# diyhue-IO.net
KiCad netlist of a schematic drawn in EAGLE
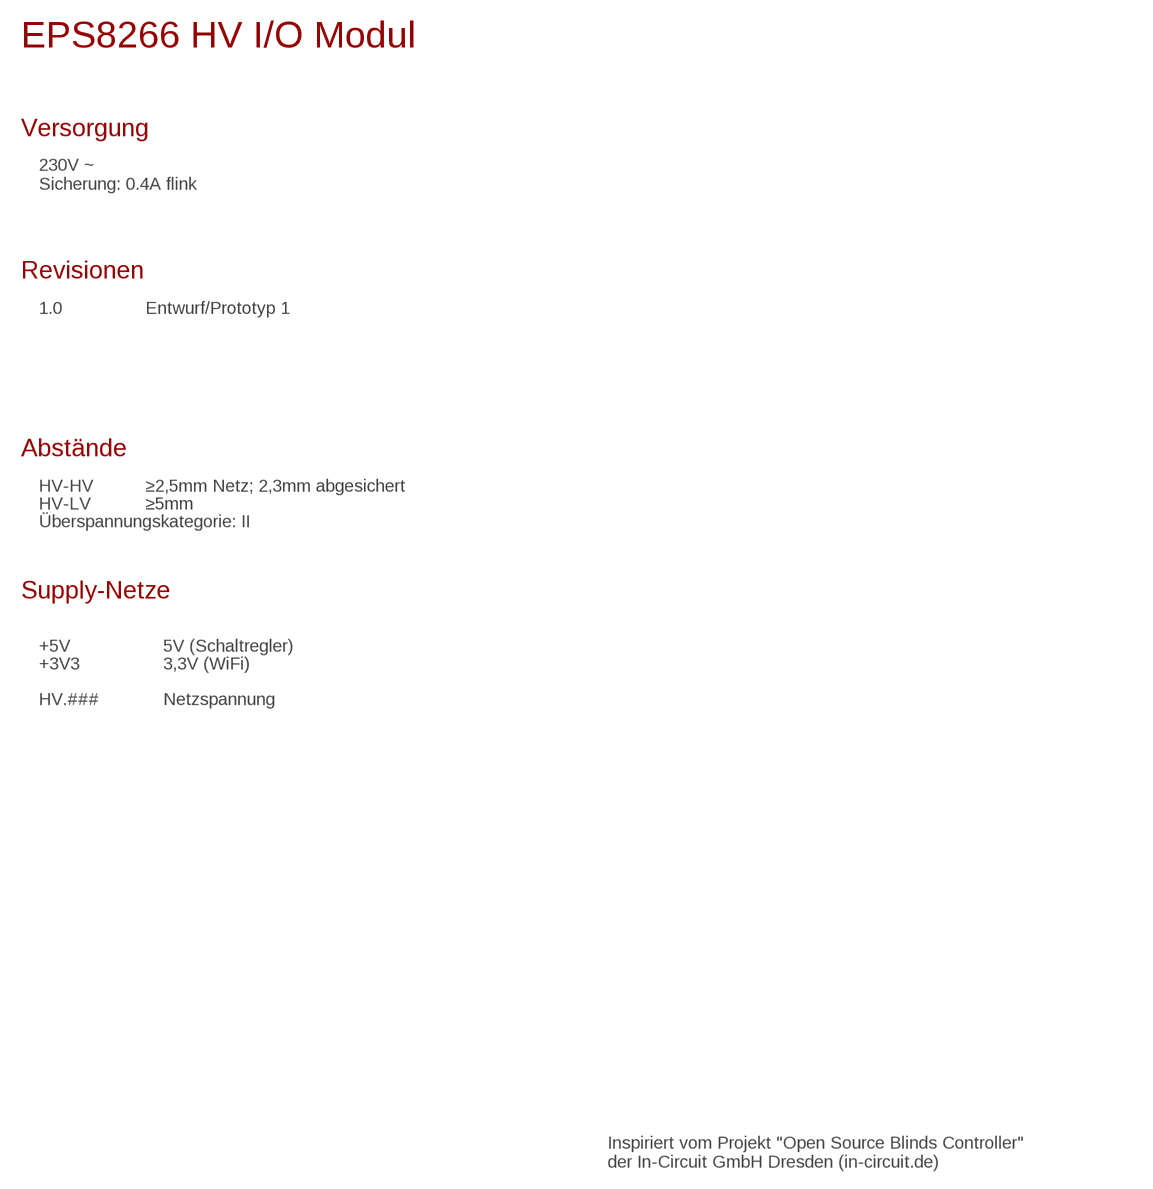
[diagram p0: schematic, sheet 1]
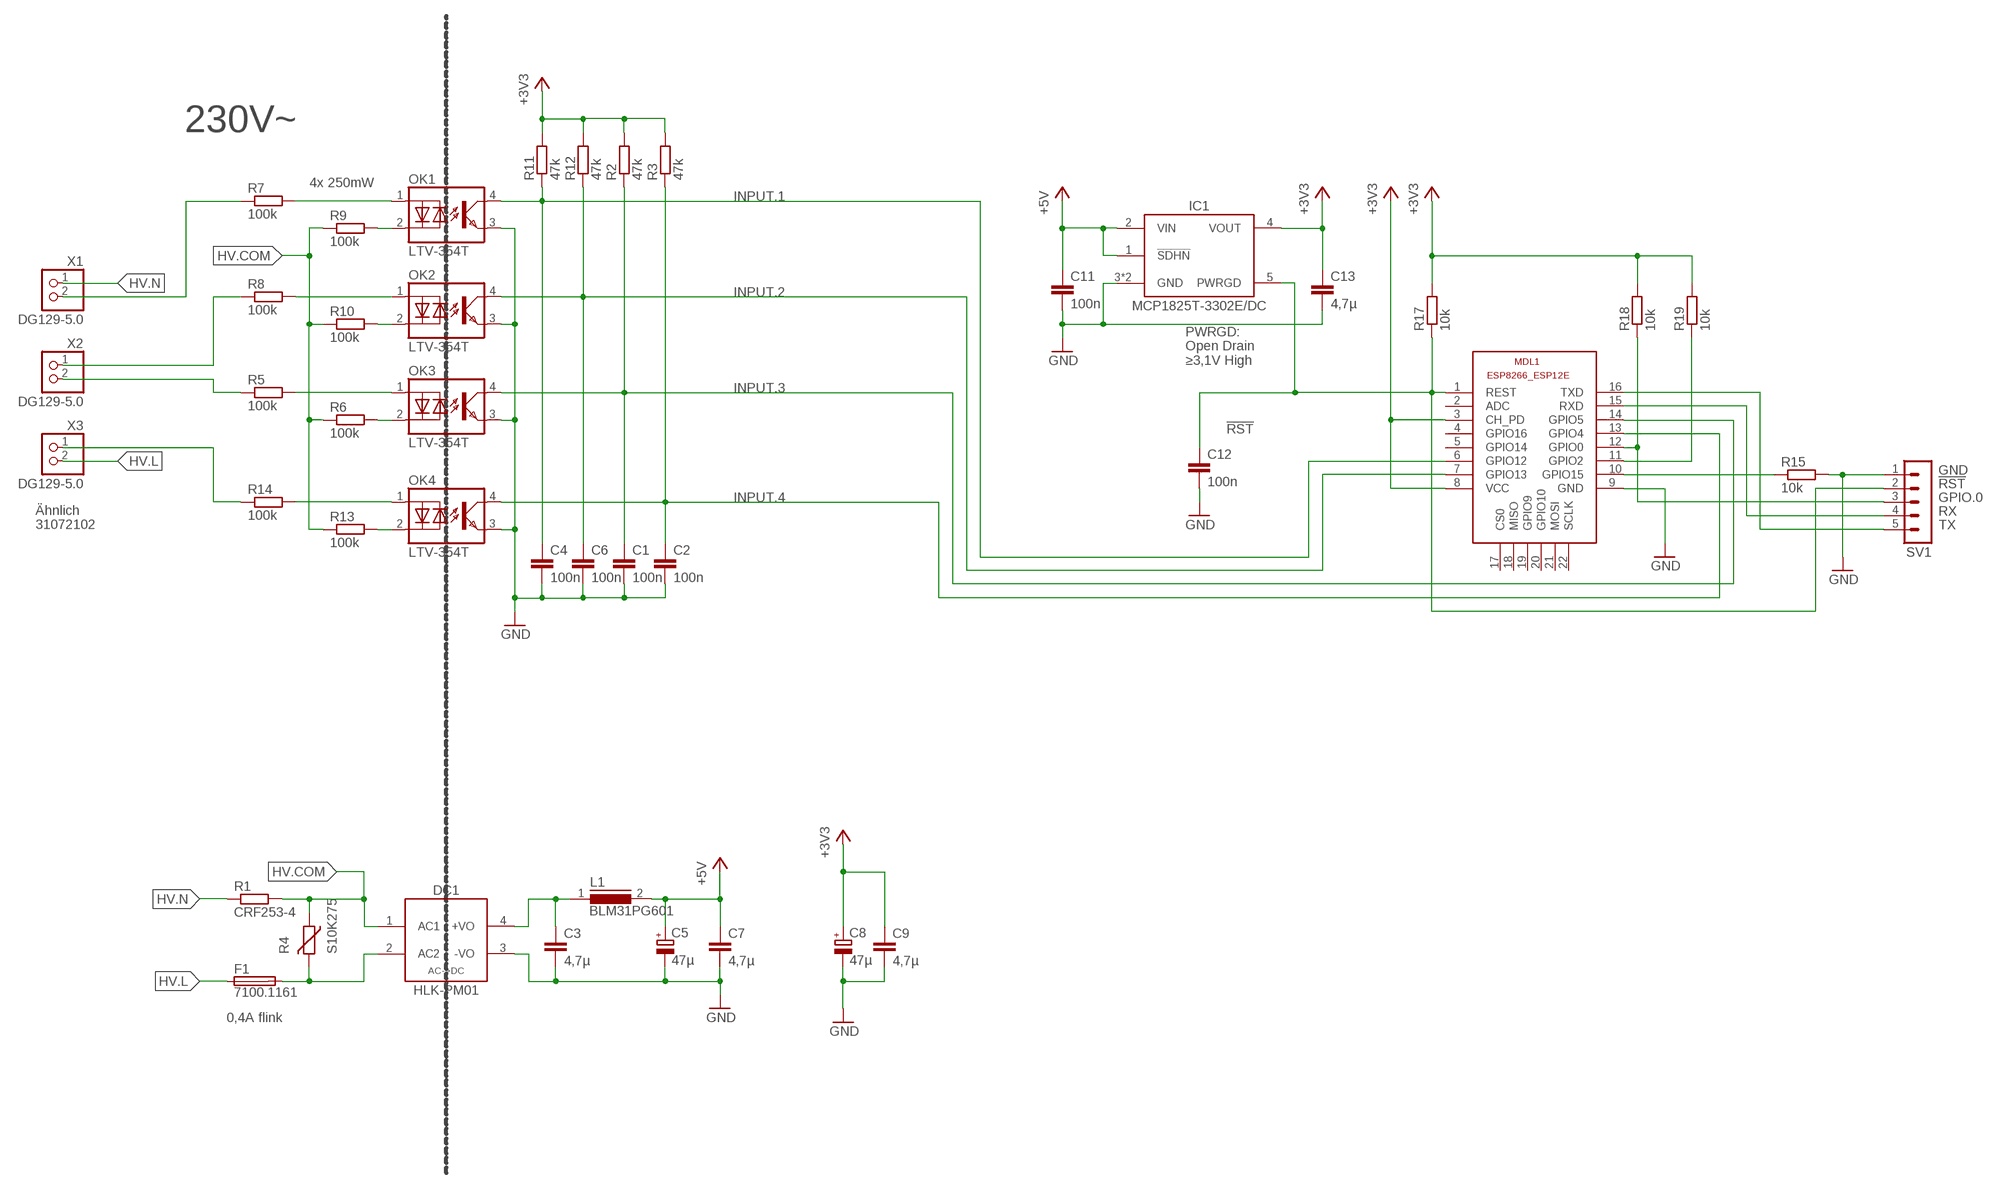
[diagram p1: schematic, sheet 2]

(export (version "E")
  (design (tool "Eeschema 10.0.6"))
  (components
    (comp (ref "C1")
      (value "100n")
      (footprint "eagle-import:C0805K")
      (libsource (lib "eagle-import") (part "C-EUC0805K"))
    )
    (comp (ref "C2")
      (value "100n")
      (footprint "eagle-import:C0805K")
      (libsource (lib "eagle-import") (part "C-EUC0805K"))
    )
    (comp (ref "C3")
      (value "4,7µ")
      (footprint "eagle-import:C0805K")
      (libsource (lib "eagle-import") (part "C-EUC0805K"))
    )
    (comp (ref "C4")
      (value "100n")
      (footprint "eagle-import:C0805K")
      (libsource (lib "eagle-import") (part "C-EUC0805K"))
    )
    (comp (ref "C5")
      (value "47µ")
      (footprint "eagle-import:E2-5")
      (libsource (lib "eagle-import") (part "CPOL-EUE2-5"))
    )
    (comp (ref "C6")
      (value "100n")
      (footprint "eagle-import:C0805K")
      (libsource (lib "eagle-import") (part "C-EUC0805K"))
    )
    (comp (ref "C7")
      (value "4,7µ")
      (footprint "eagle-import:C0805K")
      (libsource (lib "eagle-import") (part "C-EUC0805K"))
    )
    (comp (ref "C8")
      (value "47µ")
      (footprint "eagle-import:E2-5")
      (libsource (lib "eagle-import") (part "CPOL-EUE2-5"))
    )
    (comp (ref "C9")
      (value "4,7µ")
      (footprint "eagle-import:C0805K")
      (libsource (lib "eagle-import") (part "C-EUC0805K"))
    )
    (comp (ref "C11")
      (value "100n")
      (footprint "eagle-import:C0805K")
      (libsource (lib "eagle-import") (part "C-EUC0805K"))
    )
    (comp (ref "C12")
      (value "100n")
      (footprint "eagle-import:C0805K")
      (libsource (lib "eagle-import") (part "C-EUC0805K"))
    )
    (comp (ref "C13")
      (value "4,7µ")
      (footprint "eagle-import:C0805K")
      (libsource (lib "eagle-import") (part "C-EUC0805K"))
    )
    (comp (ref "DC1")
      (value "HLK-PM01")
      (footprint "eagle-import:HLK_PM01")
      (libsource (lib "eagle-import") (part "ACDC-S-HLK_PM01"))
    )
    (comp (ref "F1")
      (value "7100.1161")
      (footprint "eagle-import:SCHURTER_FRT250")
      (libsource (lib "eagle-import") (part "FUSE-FRT250"))
    )
    (comp (ref "IC1")
      (value "MCP1825T-3302E/DC")
      (footprint "eagle-import:SOT-223_5")
      (libsource (lib "eagle-import") (part "MCP1825/DC"))
    )
    (comp (ref "L1")
      (value "BLM31PG601")
      (footprint "eagle-import:BLM31P")
      (libsource (lib "eagle-import") (part "INDUCTOR-BLM31"))
    )
    (comp (ref "MDL1")
      (value "ESP8266-12EESP8266-ESP12E")
      (footprint "eagle-import:ESP8266-ESP12E")
      (libsource (lib "eagle-import") (part "ESP8266-12EESP8266-ESP12E"))
    )
    (comp (ref "OK1")
      (value "LTV-354T")
      (footprint "eagle-import:LITEON_LTV-354")
      (libsource (lib "eagle-import") (part "OC-AC_LTV-354"))
    )
    (comp (ref "OK2")
      (value "LTV-354T")
      (footprint "eagle-import:LITEON_LTV-354")
      (libsource (lib "eagle-import") (part "OC-AC_LTV-354"))
    )
    (comp (ref "OK3")
      (value "LTV-354T")
      (footprint "eagle-import:LITEON_LTV-354")
      (libsource (lib "eagle-import") (part "OC-AC_LTV-354"))
    )
    (comp (ref "OK4")
      (value "LTV-354T")
      (footprint "eagle-import:LITEON_LTV-354")
      (libsource (lib "eagle-import") (part "OC-AC_LTV-354"))
    )
    (comp (ref "R1")
      (value "CRF253-4")
      (footprint "eagle-import:0414V")
      (libsource (lib "eagle-import") (part "R-EU_0414/5V"))
    )
    (comp (ref "R2")
      (value "47k")
      (footprint "eagle-import:R0805W")
      (libsource (lib "eagle-import") (part "rcl_334_R-EU_R0805W"))
    )
    (comp (ref "R3")
      (value "47k")
      (footprint "eagle-import:R0805W")
      (libsource (lib "eagle-import") (part "rcl_334_R-EU_R0805W"))
    )
    (comp (ref "R4")
      (value "S10K275")
      (footprint "eagle-import:EPCOS_S10K275")
      (libsource (lib "eagle-import") (part "VDR-S10K275"))
    )
    (comp (ref "R5")
      (value "100k")
      (footprint "eagle-import:R1210")
      (libsource (lib "eagle-import") (part "rcl_334_R-EU_R1210"))
    )
    (comp (ref "R6")
      (value "100k")
      (footprint "eagle-import:R1210")
      (libsource (lib "eagle-import") (part "rcl_334_R-EU_R1210"))
    )
    (comp (ref "R7")
      (value "100k")
      (footprint "eagle-import:R1210")
      (libsource (lib "eagle-import") (part "rcl_334_R-EU_R1210"))
    )
    (comp (ref "R8")
      (value "100k")
      (footprint "eagle-import:R1210")
      (libsource (lib "eagle-import") (part "rcl_334_R-EU_R1210"))
    )
    (comp (ref "R9")
      (value "100k")
      (footprint "eagle-import:R1210")
      (libsource (lib "eagle-import") (part "rcl_334_R-EU_R1210"))
    )
    (comp (ref "R10")
      (value "100k")
      (footprint "eagle-import:R1210")
      (libsource (lib "eagle-import") (part "rcl_334_R-EU_R1210"))
    )
    (comp (ref "R11")
      (value "47k")
      (footprint "eagle-import:R0805W")
      (libsource (lib "eagle-import") (part "rcl_334_R-EU_R0805W"))
    )
    (comp (ref "R12")
      (value "47k")
      (footprint "eagle-import:R0805W")
      (libsource (lib "eagle-import") (part "rcl_334_R-EU_R0805W"))
    )
    (comp (ref "R13")
      (value "100k")
      (footprint "eagle-import:R1210")
      (libsource (lib "eagle-import") (part "rcl_334_R-EU_R1210"))
    )
    (comp (ref "R14")
      (value "100k")
      (footprint "eagle-import:R1210")
      (libsource (lib "eagle-import") (part "rcl_334_R-EU_R1210"))
    )
    (comp (ref "R15")
      (value "10k")
      (footprint "eagle-import:R0805W")
      (libsource (lib "eagle-import") (part "rcl_334_R-EU_R0805W"))
    )
    (comp (ref "R17")
      (value "10k")
      (footprint "eagle-import:R0805W")
      (libsource (lib "eagle-import") (part "rcl_334_R-EU_R0805W"))
    )
    (comp (ref "R18")
      (value "10k")
      (footprint "eagle-import:R0805W")
      (libsource (lib "eagle-import") (part "rcl_334_R-EU_R0805W"))
    )
    (comp (ref "R19")
      (value "10k")
      (footprint "eagle-import:R0805W")
      (libsource (lib "eagle-import") (part "rcl_334_R-EU_R0805W"))
    )
    (comp (ref "SV1")
      (value "MA05-1")
      (footprint "eagle-import:MA05-1")
      (libsource (lib "eagle-import") (part "MA05-1"))
    )
    (comp (ref "X1")
      (value "DG129-5.0")
      (footprint "eagle-import:31012102")
      (libsource (lib "eagle-import") (part "1PIN-2-31012102"))
    )
    (comp (ref "X2")
      (value "DG129-5.0")
      (footprint "eagle-import:31012102")
      (libsource (lib "eagle-import") (part "1PIN-2-31012102"))
    )
    (comp (ref "X3")
      (value "DG129-5.0")
      (footprint "eagle-import:31012102")
      (libsource (lib "eagle-import") (part "1PIN-2-31012102"))
    )
  )
  (nets
    (net (code "1") (name "+3V3") (class "Default")
      (node (ref "C13") (pin "1") (pinfunction "1_1") (pintype "passive"))
      (node (ref "C8") (pin "+") (pinfunction "+_+") (pintype "passive"))
      (node (ref "C9") (pin "1") (pinfunction "1_1") (pintype "passive"))
      (node (ref "IC1") (pin "4") (pinfunction "VOUT_4") (pintype "passive"))
      (node (ref "MDL1") (pin "3") (pinfunction "CH_PD_3") (pintype "bidirectional"))
      (node (ref "MDL1") (pin "8") (pinfunction "VCC_8") (pintype "bidirectional"))
      (node (ref "R11") (pin "2") (pinfunction "2_2") (pintype "passive"))
      (node (ref "R12") (pin "2") (pinfunction "2_2") (pintype "passive"))
      (node (ref "R17") (pin "2") (pinfunction "2_2") (pintype "passive"))
      (node (ref "R18") (pin "2") (pinfunction "2_2") (pintype "passive"))
      (node (ref "R19") (pin "2") (pinfunction "2_2") (pintype "passive"))
      (node (ref "R2") (pin "2") (pinfunction "2_2") (pintype "passive"))
      (node (ref "R3") (pin "2") (pinfunction "2_2") (pintype "passive"))
    )
    (net (code "2") (name "+5V") (class "Default")
      (node (ref "C11") (pin "1") (pinfunction "1_1") (pintype "passive"))
      (node (ref "C5") (pin "+") (pinfunction "+_+") (pintype "passive"))
      (node (ref "C7") (pin "1") (pinfunction "1_1") (pintype "passive"))
      (node (ref "IC1") (pin "1") (pinfunction "~{SDHN}_1") (pintype "input"))
      (node (ref "IC1") (pin "2") (pinfunction "VIN_2") (pintype "power_in"))
      (node (ref "L1") (pin "2") (pinfunction "2_2") (pintype "passive"))
    )
    (net (code "3") (name "GND") (class "Default")
      (node (ref "C1") (pin "2") (pinfunction "2_2") (pintype "passive"))
      (node (ref "C11") (pin "2") (pinfunction "2_2") (pintype "passive"))
      (node (ref "C12") (pin "2") (pinfunction "2_2") (pintype "passive"))
      (node (ref "C13") (pin "2") (pinfunction "2_2") (pintype "passive"))
      (node (ref "C2") (pin "2") (pinfunction "2_2") (pintype "passive"))
      (node (ref "C3") (pin "2") (pinfunction "2_2") (pintype "passive"))
      (node (ref "C4") (pin "2") (pinfunction "2_2") (pintype "passive"))
      (node (ref "C5") (pin "-") (pinfunction "-_-") (pintype "passive"))
      (node (ref "C6") (pin "2") (pinfunction "2_2") (pintype "passive"))
      (node (ref "C7") (pin "2") (pinfunction "2_2") (pintype "passive"))
      (node (ref "C8") (pin "-") (pinfunction "-_-") (pintype "passive"))
      (node (ref "C9") (pin "2") (pinfunction "2_2") (pintype "passive"))
      (node (ref "DC1") (pin "3") (pinfunction "-VO_3") (pintype "passive"))
      (node (ref "IC1") (pin "3") (pinfunction "GND_3") (pintype "power_in"))
      (node (ref "IC1") (pin "6") (pinfunction "GND_6") (pintype "power_in"))
      (node (ref "MDL1") (pin "9") (pinfunction "GND_9") (pintype "bidirectional"))
      (node (ref "OK1") (pin "3") (pinfunction "E_3") (pintype "passive"))
      (node (ref "OK2") (pin "3") (pinfunction "E_3") (pintype "passive"))
      (node (ref "OK3") (pin "3") (pinfunction "E_3") (pintype "passive"))
      (node (ref "OK4") (pin "3") (pinfunction "E_3") (pintype "passive"))
      (node (ref "R15") (pin "2") (pinfunction "2_2") (pintype "passive"))
      (node (ref "SV1") (pin "1") (pinfunction "1_1") (pintype "passive"))
    )
    (net (code "4") (name "GPIO.0") (class "Default")
      (node (ref "MDL1") (pin "12") (pinfunction "GPIO0_12") (pintype "bidirectional"))
      (node (ref "R18") (pin "1") (pinfunction "1_1") (pintype "passive"))
      (node (ref "SV1") (pin "3") (pinfunction "3_3") (pintype "passive"))
    )
    (net (code "5") (name "HV.COM") (class "Default")
      (node (ref "DC1") (pin "1") (pinfunction "AC1_1") (pintype "power_in"))
      (node (ref "R1") (pin "2") (pinfunction "2_2") (pintype "passive"))
      (node (ref "R10") (pin "1") (pinfunction "1_1") (pintype "passive"))
      (node (ref "R13") (pin "1") (pinfunction "1_1") (pintype "passive"))
      (node (ref "R4") (pin "1") (pinfunction "1_1") (pintype "passive"))
      (node (ref "R6") (pin "1") (pinfunction "1_1") (pintype "passive"))
      (node (ref "R9") (pin "1") (pinfunction "1_1") (pintype "passive"))
    )
    (net (code "6") (name "HV.L") (class "Default")
      (node (ref "F1") (pin "1") (pinfunction "1_1") (pintype "passive"))
      (node (ref "X3") (pin "2") (pinfunction "2_2") (pintype "passive"))
    )
    (net (code "7") (name "HV.N") (class "Default")
      (node (ref "R1") (pin "1") (pinfunction "1_1") (pintype "passive"))
      (node (ref "X1") (pin "1") (pinfunction "1_1") (pintype "passive"))
    )
    (net (code "8") (name "INPUT.1") (class "Default")
      (node (ref "C4") (pin "1") (pinfunction "1_1") (pintype "passive"))
      (node (ref "MDL1") (pin "6") (pinfunction "GPIO12_6") (pintype "bidirectional"))
      (node (ref "OK1") (pin "4") (pinfunction "C_4") (pintype "passive"))
      (node (ref "R11") (pin "1") (pinfunction "1_1") (pintype "passive"))
    )
    (net (code "9") (name "INPUT.2") (class "Default")
      (node (ref "C6") (pin "1") (pinfunction "1_1") (pintype "passive"))
      (node (ref "MDL1") (pin "7") (pinfunction "GPIO13_7") (pintype "bidirectional"))
      (node (ref "OK2") (pin "4") (pinfunction "C_4") (pintype "passive"))
      (node (ref "R12") (pin "1") (pinfunction "1_1") (pintype "passive"))
    )
    (net (code "10") (name "INPUT.3") (class "Default")
      (node (ref "C1") (pin "1") (pinfunction "1_1") (pintype "passive"))
      (node (ref "MDL1") (pin "14") (pinfunction "GPIO5_14") (pintype "bidirectional"))
      (node (ref "OK3") (pin "4") (pinfunction "C_4") (pintype "passive"))
      (node (ref "R2") (pin "1") (pinfunction "1_1") (pintype "passive"))
    )
    (net (code "11") (name "INPUT.4") (class "Default")
      (node (ref "C2") (pin "1") (pinfunction "1_1") (pintype "passive"))
      (node (ref "MDL1") (pin "13") (pinfunction "GPIO4_13") (pintype "bidirectional"))
      (node (ref "OK4") (pin "4") (pinfunction "C_4") (pintype "passive"))
      (node (ref "R3") (pin "1") (pinfunction "1_1") (pintype "passive"))
    )
    (net (code "12") (name "Net-(DC1-+VO)") (class "Default")
      (node (ref "C3") (pin "1") (pinfunction "1_1") (pintype "passive"))
      (node (ref "DC1") (pin "4") (pinfunction "+VO_4") (pintype "passive"))
      (node (ref "L1") (pin "1") (pinfunction "1_1") (pintype "passive"))
    )
    (net (code "13") (name "Net-(DC1-AC2)") (class "Default")
      (node (ref "DC1") (pin "2") (pinfunction "AC2_2") (pintype "power_in"))
      (node (ref "F1") (pin "2") (pinfunction "2_2") (pintype "passive"))
      (node (ref "R4") (pin "2") (pinfunction "2_2") (pintype "passive"))
    )
    (net (code "14") (name "Net-(MDL1-GPIO2)") (class "Default")
      (node (ref "MDL1") (pin "11") (pinfunction "GPIO2_11") (pintype "bidirectional"))
      (node (ref "R19") (pin "1") (pinfunction "1_1") (pintype "passive"))
    )
    (net (code "15") (name "Net-(MDL1-GPIO15)") (class "Default")
      (node (ref "MDL1") (pin "10") (pinfunction "GPIO15_10") (pintype "bidirectional"))
      (node (ref "R15") (pin "1") (pinfunction "1_1") (pintype "passive"))
    )
    (net (code "16") (name "Net-(OK1-AC)") (class "Default")
      (node (ref "OK1") (pin "1") (pinfunction "AC_1") (pintype "passive"))
      (node (ref "R7") (pin "2") (pinfunction "2_2") (pintype "passive"))
    )
    (net (code "17") (name "Net-(OK1-CA)") (class "Default")
      (node (ref "OK1") (pin "2") (pinfunction "CA_2") (pintype "passive"))
      (node (ref "R9") (pin "2") (pinfunction "2_2") (pintype "passive"))
    )
    (net (code "18") (name "Net-(OK2-AC)") (class "Default")
      (node (ref "OK2") (pin "1") (pinfunction "AC_1") (pintype "passive"))
      (node (ref "R8") (pin "2") (pinfunction "2_2") (pintype "passive"))
    )
    (net (code "19") (name "Net-(OK2-CA)") (class "Default")
      (node (ref "OK2") (pin "2") (pinfunction "CA_2") (pintype "passive"))
      (node (ref "R10") (pin "2") (pinfunction "2_2") (pintype "passive"))
    )
    (net (code "20") (name "Net-(OK3-AC)") (class "Default")
      (node (ref "OK3") (pin "1") (pinfunction "AC_1") (pintype "passive"))
      (node (ref "R5") (pin "2") (pinfunction "2_2") (pintype "passive"))
    )
    (net (code "21") (name "Net-(OK3-CA)") (class "Default")
      (node (ref "OK3") (pin "2") (pinfunction "CA_2") (pintype "passive"))
      (node (ref "R6") (pin "2") (pinfunction "2_2") (pintype "passive"))
    )
    (net (code "22") (name "Net-(OK4-AC)") (class "Default")
      (node (ref "OK4") (pin "1") (pinfunction "AC_1") (pintype "passive"))
      (node (ref "R14") (pin "2") (pinfunction "2_2") (pintype "passive"))
    )
    (net (code "23") (name "Net-(OK4-CA)") (class "Default")
      (node (ref "OK4") (pin "2") (pinfunction "CA_2") (pintype "passive"))
      (node (ref "R13") (pin "2") (pinfunction "2_2") (pintype "passive"))
    )
    (net (code "24") (name "Net-(R5-Pad1)") (class "Default")
      (node (ref "R5") (pin "1") (pinfunction "1_1") (pintype "passive"))
      (node (ref "X2") (pin "2") (pinfunction "2_2") (pintype "passive"))
    )
    (net (code "25") (name "Net-(R7-Pad1)") (class "Default")
      (node (ref "R7") (pin "1") (pinfunction "1_1") (pintype "passive"))
      (node (ref "X1") (pin "2") (pinfunction "2_2") (pintype "passive"))
    )
    (net (code "26") (name "Net-(R8-Pad1)") (class "Default")
      (node (ref "R8") (pin "1") (pinfunction "1_1") (pintype "passive"))
      (node (ref "X2") (pin "1") (pinfunction "1_1") (pintype "passive"))
    )
    (net (code "27") (name "Net-(R14-Pad1)") (class "Default")
      (node (ref "R14") (pin "1") (pinfunction "1_1") (pintype "passive"))
      (node (ref "X3") (pin "1") (pinfunction "1_1") (pintype "passive"))
    )
    (net (code "28") (name "RX") (class "Default")
      (node (ref "MDL1") (pin "15") (pinfunction "RXD_15") (pintype "bidirectional"))
      (node (ref "SV1") (pin "4") (pinfunction "4_4") (pintype "passive"))
    )
    (net (code "29") (name "TX") (class "Default")
      (node (ref "MDL1") (pin "16") (pinfunction "TXD_16") (pintype "bidirectional"))
      (node (ref "SV1") (pin "5") (pinfunction "5_5") (pintype "passive"))
    )
    (net (code "30") (name "unconnected-(MDL1-ADC-Pad2)") (class "Default")
      (node (ref "MDL1") (pin "2") (pinfunction "ADC_2") (pintype "bidirectional"))
    )
    (net (code "31") (name "unconnected-(MDL1-CS0-Pad17)") (class "Default")
      (node (ref "MDL1") (pin "17") (pinfunction "CS0_17") (pintype "bidirectional"))
    )
    (net (code "32") (name "unconnected-(MDL1-GPIO9-Pad19)") (class "Default")
      (node (ref "MDL1") (pin "19") (pinfunction "GPIO9_19") (pintype "bidirectional"))
    )
    (net (code "33") (name "unconnected-(MDL1-GPIO10-Pad20)") (class "Default")
      (node (ref "MDL1") (pin "20") (pinfunction "GPIO10_20") (pintype "bidirectional"))
    )
    (net (code "34") (name "unconnected-(MDL1-GPIO14-Pad5)") (class "Default")
      (node (ref "MDL1") (pin "5") (pinfunction "GPIO14_5") (pintype "bidirectional"))
    )
    (net (code "35") (name "unconnected-(MDL1-GPIO16-Pad4)") (class "Default")
      (node (ref "MDL1") (pin "4") (pinfunction "GPIO16_4") (pintype "bidirectional"))
    )
    (net (code "36") (name "unconnected-(MDL1-MISO-Pad18)") (class "Default")
      (node (ref "MDL1") (pin "18") (pinfunction "MISO_18") (pintype "bidirectional"))
    )
    (net (code "37") (name "unconnected-(MDL1-MOSI-Pad21)") (class "Default")
      (node (ref "MDL1") (pin "21") (pinfunction "MOSI_21") (pintype "bidirectional"))
    )
    (net (code "38") (name "unconnected-(MDL1-SCLK-Pad22)") (class "Default")
      (node (ref "MDL1") (pin "22") (pinfunction "SCLK_22") (pintype "bidirectional"))
    )
    (net (code "39") (name "~{RST}") (class "Default")
      (node (ref "C12") (pin "1") (pinfunction "1_1") (pintype "passive"))
      (node (ref "IC1") (pin "5") (pinfunction "PWRGD_5") (pintype "open_collector"))
      (node (ref "MDL1") (pin "1") (pinfunction "REST_1") (pintype "bidirectional"))
      (node (ref "R17") (pin "1") (pinfunction "1_1") (pintype "passive"))
      (node (ref "SV1") (pin "2") (pinfunction "2_2") (pintype "passive"))
    )
  )
)
